# 5_cyber60-smk_periferals.net
KiCad netlist of a schematic drawn in Altium Designer
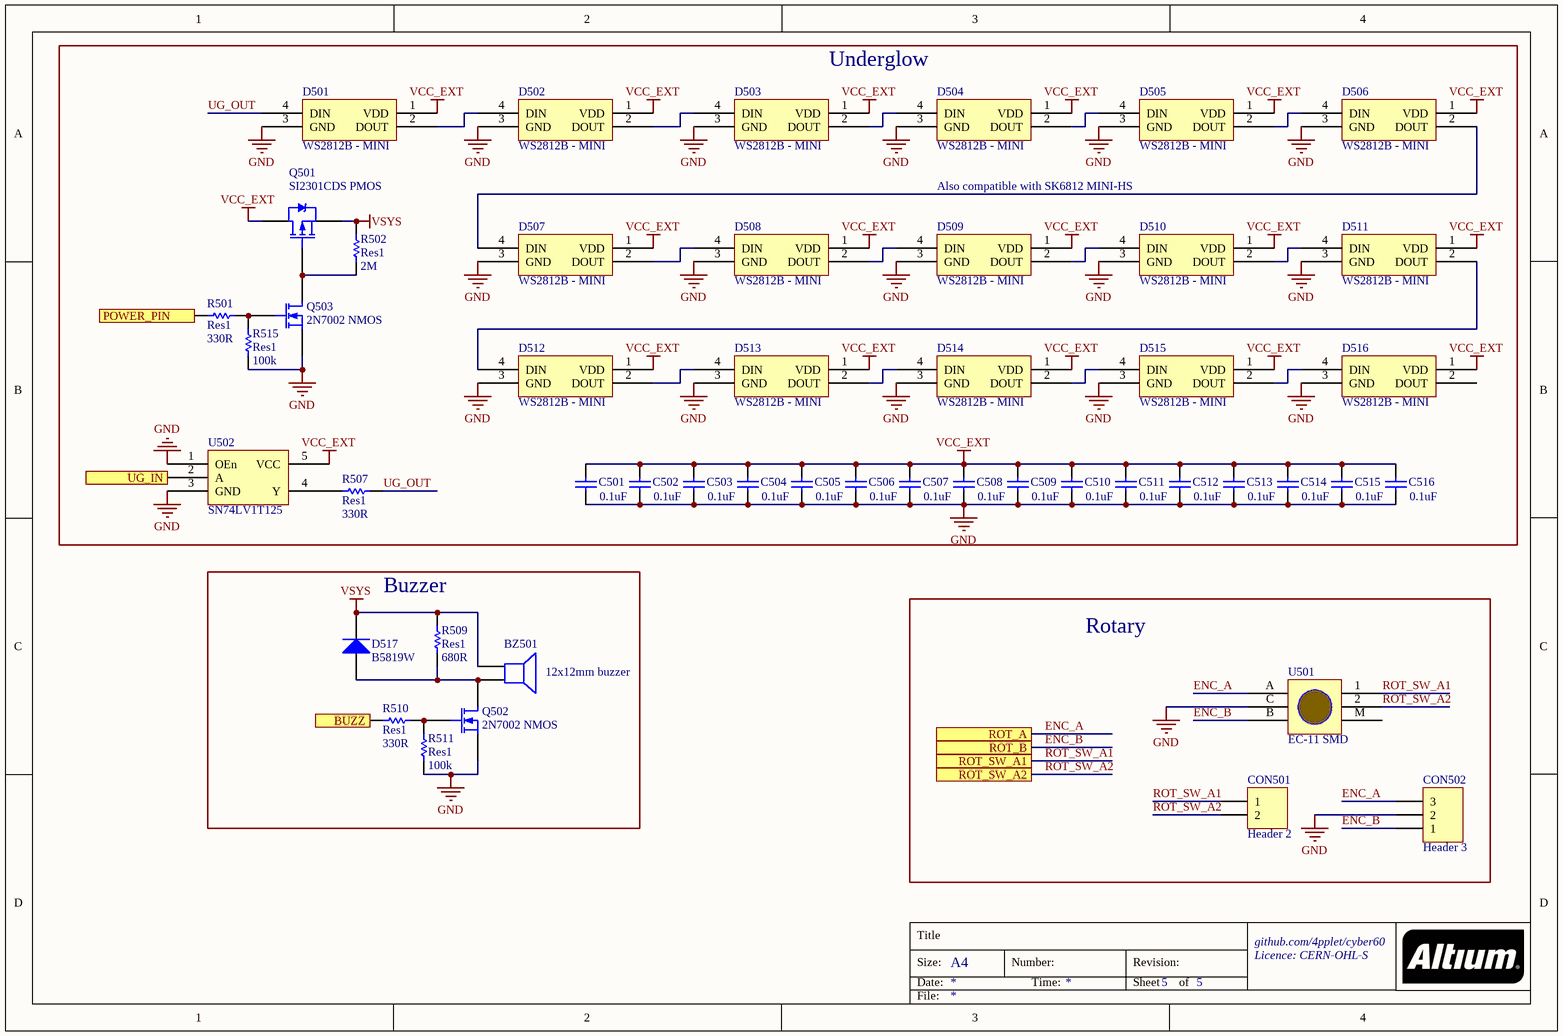
[diagram p0: 5_cyber60-smk_periferals.SchDoc]

(export (version "E")
  (design (tool "Eeschema 10.0.6"))
  (components
    (comp (ref "BZ501")
      (value "12x12mm buzzer")
      (footprint "buzzer 12x12")
      (description "Loudspeaker")
      (fields (field (name "LCSC PART #") "C409829") (field (name "MRF.PART") "YS-SBZ1230"))
      (libsource (lib "Miscellaneous Devices") (part "Speaker"))
    )
    (comp (ref "C501")
      (value "0.1uF")
      (footprint "C0603[1608]")
      (description "Capacitor")
      (fields (field (name "MFG") "KEMET") (field (name "LCSC PART #") "C14663"))
      (libsource (lib "Miscellaneous Devices") (part "Cap"))
    )
    (comp (ref "C502")
      (value "0.1uF")
      (footprint "C0603[1608]")
      (description "Capacitor")
      (fields (field (name "MFG") "KEMET") (field (name "LCSC PART #") "C14663"))
      (libsource (lib "Miscellaneous Devices") (part "Cap"))
    )
    (comp (ref "C503")
      (value "0.1uF")
      (footprint "C0603[1608]")
      (description "Capacitor")
      (fields (field (name "MFG") "KEMET") (field (name "LCSC PART #") "C14663"))
      (libsource (lib "Miscellaneous Devices") (part "Cap"))
    )
    (comp (ref "C504")
      (value "0.1uF")
      (footprint "C0603[1608]")
      (description "Capacitor")
      (fields (field (name "MFG") "KEMET") (field (name "LCSC PART #") "C14663"))
      (libsource (lib "Miscellaneous Devices") (part "Cap"))
    )
    (comp (ref "C505")
      (value "0.1uF")
      (footprint "C0603[1608]")
      (description "Capacitor")
      (fields (field (name "MFG") "KEMET") (field (name "LCSC PART #") "C14663"))
      (libsource (lib "Miscellaneous Devices") (part "Cap"))
    )
    (comp (ref "C506")
      (value "0.1uF")
      (footprint "C0603[1608]")
      (description "Capacitor")
      (fields (field (name "MFG") "KEMET") (field (name "LCSC PART #") "C14663"))
      (libsource (lib "Miscellaneous Devices") (part "Cap"))
    )
    (comp (ref "C507")
      (value "0.1uF")
      (footprint "C0603[1608]")
      (description "Capacitor")
      (fields (field (name "MFG") "KEMET") (field (name "LCSC PART #") "C14663"))
      (libsource (lib "Miscellaneous Devices") (part "Cap"))
    )
    (comp (ref "C508")
      (value "0.1uF")
      (footprint "C0603[1608]")
      (description "Capacitor")
      (fields (field (name "MFG") "KEMET") (field (name "LCSC PART #") "C14663"))
      (libsource (lib "Miscellaneous Devices") (part "Cap"))
    )
    (comp (ref "C509")
      (value "0.1uF")
      (footprint "C0603[1608]")
      (description "Capacitor")
      (fields (field (name "MFG") "KEMET") (field (name "LCSC PART #") "C14663"))
      (libsource (lib "Miscellaneous Devices") (part "Cap"))
    )
    (comp (ref "C510")
      (value "0.1uF")
      (footprint "C0603[1608]")
      (description "Capacitor")
      (fields (field (name "MFG") "KEMET") (field (name "LCSC PART #") "C14663"))
      (libsource (lib "Miscellaneous Devices") (part "Cap"))
    )
    (comp (ref "C511")
      (value "0.1uF")
      (footprint "C0603[1608]")
      (description "Capacitor")
      (fields (field (name "MFG") "KEMET") (field (name "LCSC PART #") "C14663"))
      (libsource (lib "Miscellaneous Devices") (part "Cap"))
    )
    (comp (ref "C512")
      (value "0.1uF")
      (footprint "C0603[1608]")
      (description "Capacitor")
      (fields (field (name "MFG") "KEMET") (field (name "LCSC PART #") "C14663"))
      (libsource (lib "Miscellaneous Devices") (part "Cap"))
    )
    (comp (ref "C513")
      (value "0.1uF")
      (footprint "C0603[1608]")
      (description "Capacitor")
      (fields (field (name "MFG") "KEMET") (field (name "LCSC PART #") "C14663"))
      (libsource (lib "Miscellaneous Devices") (part "Cap"))
    )
    (comp (ref "C514")
      (value "0.1uF")
      (footprint "C0603[1608]")
      (description "Capacitor")
      (fields (field (name "MFG") "KEMET") (field (name "LCSC PART #") "C14663"))
      (libsource (lib "Miscellaneous Devices") (part "Cap"))
    )
    (comp (ref "C515")
      (value "0.1uF")
      (footprint "C0603[1608]")
      (description "Capacitor")
      (fields (field (name "MFG") "KEMET") (field (name "LCSC PART #") "C14663"))
      (libsource (lib "Miscellaneous Devices") (part "Cap"))
    )
    (comp (ref "C516")
      (value "0.1uF")
      (footprint "C0603[1608]")
      (description "Capacitor")
      (fields (field (name "MFG") "KEMET") (field (name "LCSC PART #") "C14663"))
      (libsource (lib "Miscellaneous Devices") (part "Cap"))
    )
    (comp (ref "CON501")
      (value "Header 2")
      (footprint "HDR1X2")
      (description "Header, 2-Pin")
      (libsource (lib "Miscellaneous Connectors") (part "Header 2"))
    )
    (comp (ref "CON502")
      (value "Header 3")
      (footprint "HDR1X3")
      (description "Header, 3-Pin")
      (libsource (lib "Miscellaneous Connectors") (part "Header 3"))
    )
    (comp (ref "D501")
      (value "WS2812B - MINI")
      (footprint "WS2812B - 2020")
      (fields (field (name "LCSC PART #") "C965556") (field (name "MRF.PART") "WS2812C-2020"))
      (libsource (lib "Keebs") (part "WS2812B"))
    )
    (comp (ref "D502")
      (value "WS2812B - MINI")
      (footprint "WS2812B - 2020")
      (fields (field (name "LCSC PART #") "C965556") (field (name "MRF.PART") "WS2812C-2020"))
      (libsource (lib "Keebs") (part "WS2812B"))
    )
    (comp (ref "D503")
      (value "WS2812B - MINI")
      (footprint "WS2812B - 2020")
      (fields (field (name "LCSC PART #") "C965556") (field (name "MRF.PART") "WS2812C-2020"))
      (libsource (lib "Keebs") (part "WS2812B"))
    )
    (comp (ref "D504")
      (value "WS2812B - MINI")
      (footprint "WS2812B - 2020")
      (fields (field (name "LCSC PART #") "C965556") (field (name "MRF.PART") "WS2812C-2020"))
      (libsource (lib "Keebs") (part "WS2812B"))
    )
    (comp (ref "D505")
      (value "WS2812B - MINI")
      (footprint "WS2812B - 2020")
      (fields (field (name "LCSC PART #") "C965556") (field (name "MRF.PART") "WS2812C-2020"))
      (libsource (lib "Keebs") (part "WS2812B"))
    )
    (comp (ref "D506")
      (value "WS2812B - MINI")
      (footprint "WS2812B - 2020")
      (fields (field (name "LCSC PART #") "C965556") (field (name "MRF.PART") "WS2812C-2020"))
      (libsource (lib "Keebs") (part "WS2812B"))
    )
    (comp (ref "D507")
      (value "WS2812B - MINI")
      (footprint "WS2812B - 2020")
      (fields (field (name "LCSC PART #") "C965556") (field (name "MRF.PART") "WS2812C-2020"))
      (libsource (lib "Keebs") (part "WS2812B"))
    )
    (comp (ref "D508")
      (value "WS2812B - MINI")
      (footprint "WS2812B - 2020")
      (fields (field (name "LCSC PART #") "C965556") (field (name "MRF.PART") "WS2812C-2020"))
      (libsource (lib "Keebs") (part "WS2812B"))
    )
    (comp (ref "D509")
      (value "WS2812B - MINI")
      (footprint "WS2812B - 2020")
      (fields (field (name "LCSC PART #") "C965556") (field (name "MRF.PART") "WS2812C-2020"))
      (libsource (lib "Keebs") (part "WS2812B"))
    )
    (comp (ref "D510")
      (value "WS2812B - MINI")
      (footprint "WS2812B - 2020")
      (fields (field (name "LCSC PART #") "C965556") (field (name "MRF.PART") "WS2812C-2020"))
      (libsource (lib "Keebs") (part "WS2812B"))
    )
    (comp (ref "D511")
      (value "WS2812B - MINI")
      (footprint "WS2812B - 2020")
      (fields (field (name "LCSC PART #") "C965556") (field (name "MRF.PART") "WS2812C-2020"))
      (libsource (lib "Keebs") (part "WS2812B"))
    )
    (comp (ref "D512")
      (value "WS2812B - MINI")
      (footprint "WS2812B - 2020")
      (fields (field (name "LCSC PART #") "C965556") (field (name "MRF.PART") "WS2812C-2020"))
      (libsource (lib "Keebs") (part "WS2812B"))
    )
    (comp (ref "D513")
      (value "WS2812B - MINI")
      (footprint "WS2812B - 2020")
      (fields (field (name "LCSC PART #") "C965556") (field (name "MRF.PART") "WS2812C-2020"))
      (libsource (lib "Keebs") (part "WS2812B"))
    )
    (comp (ref "D514")
      (value "WS2812B - MINI")
      (footprint "WS2812B - 2020")
      (fields (field (name "LCSC PART #") "C965556") (field (name "MRF.PART") "WS2812C-2020"))
      (libsource (lib "Keebs") (part "WS2812B"))
    )
    (comp (ref "D515")
      (value "WS2812B - MINI")
      (footprint "WS2812B - 2020")
      (fields (field (name "LCSC PART #") "C965556") (field (name "MRF.PART") "WS2812C-2020"))
      (libsource (lib "Keebs") (part "WS2812B"))
    )
    (comp (ref "D516")
      (value "WS2812B - MINI")
      (footprint "WS2812B - 2020")
      (fields (field (name "LCSC PART #") "C965556") (field (name "MRF.PART") "WS2812C-2020"))
      (libsource (lib "Keebs") (part "WS2812B"))
    )
    (comp (ref "D517")
      (value "B5819W")
      (footprint "SOD-123")
      (description "Default Diode")
      (fields (field (name "LCSC PART #") "C8598"))
      (libsource (lib "Miscellaneous Devices") (part "Diode"))
    )
    (comp (ref "Q501")
      (value "SI2301CDS PMOS")
      (footprint "SOT-23-3")
      (description "P-Channel Power MOSFET")
      (fields (field (name "MRF.PART") "SI2301CDS-T1-GE3") (field (name "LCSC PART #") "C10487"))
      (libsource (lib "Miscellaneous Devices") (part "PMOS-2"))
    )
    (comp (ref "Q502")
      (value "2N7002 NMOS")
      (footprint "SOT-23-3")
      (description "N-Channel MOSFET")
      (fields (field (name "LCSC PART #") "C8545") (field (name "MRF.PART") "2N7002"))
      (libsource (lib "Miscellaneous Devices") (part "MOSFET-N"))
    )
    (comp (ref "Q503")
      (value "2N7002 NMOS")
      (footprint "SOT-23-3")
      (description "N-Channel MOSFET")
      (fields (field (name "LCSC PART #") "C8545") (field (name "MRF.PART") "2N7002"))
      (libsource (lib "Miscellaneous Devices") (part "MOSFET-N"))
    )
    (comp (ref "R501")
      (value "Res1")
      (footprint "R0603[1608]")
      (description "Resistor")
      (fields
        (field (name "ALTIUM_VALUE") "330R")
        (field (name "LCSC PART #") "C23138")
        (field (name "MRF.PART") "0603WAF3300T5E")
      )
      (libsource (lib "Miscellaneous Devices") (part "Res1"))
    )
    (comp (ref "R502")
      (value "Res1")
      (footprint "R0603[1608]")
      (description "Resistor")
      (fields
        (field (name "ALTIUM_VALUE") "2M")
        (field (name "MRF.PART") "0603WAF2004T5E")
        (field (name "LCSC PART #") "C22976")
      )
      (libsource (lib "Miscellaneous Devices") (part "Res1"))
    )
    (comp (ref "R507")
      (value "Res1")
      (footprint "R0603[1608]")
      (description "Resistor")
      (fields
        (field (name "ALTIUM_VALUE") "330R")
        (field (name "LCSC PART #") "C23138")
        (field (name "MRF.PART") "0603WAF3300T5E")
      )
      (libsource (lib "Miscellaneous Devices") (part "Res1"))
    )
    (comp (ref "R509")
      (value "Res1")
      (footprint "R0603[1608]")
      (description "Resistor")
      (fields
        (field (name "ALTIUM_VALUE") "680R")
        (field (name "MRF.PART") "0603WAF6800T5E")
        (field (name "LCSC PART #") "C23228")
      )
      (libsource (lib "Miscellaneous Devices") (part "Res1"))
    )
    (comp (ref "R510")
      (value "Res1")
      (footprint "R0603[1608]")
      (description "Resistor")
      (fields
        (field (name "ALTIUM_VALUE") "330R")
        (field (name "LCSC PART #") "C23138")
        (field (name "MRF.PART") "0603WAF3300T5E")
      )
      (libsource (lib "Miscellaneous Devices") (part "Res1"))
    )
    (comp (ref "R511")
      (value "Res1")
      (footprint "R0603[1608]")
      (description "Resistor")
      (fields
        (field (name "ALTIUM_VALUE") "100k")
        (field (name "MRF.PART") "0603WAF1003T5E")
        (field (name "LCSC PART #") "C25803")
      )
      (libsource (lib "Miscellaneous Devices") (part "Res1"))
    )
    (comp (ref "R515")
      (value "Res1")
      (footprint "R0603[1608]")
      (description "Resistor")
      (fields
        (field (name "ALTIUM_VALUE") "100k")
        (field (name "MRF.PART") "0603WAF1003T5E")
        (field (name "LCSC PART #") "C25803")
      )
      (libsource (lib "Miscellaneous Devices") (part "Res1"))
    )
    (comp (ref "U501") (value "EC-11 SMD") (footprint "EC11-SMD") (libsource (lib "Keebs") (part "EC-11")))
    (comp (ref "U502")
      (value "SN74LV1T125")
      (footprint "SOT-23-5")
      (description "SN74LV1T125 or SN74LV1T34. Connect OE to GND")
      (fields (field (name "LCSC PART #") "C473338") (field (name "MRF.PART") "SN74LV1T125DBVR"))
      (libsource (lib "Keebs") (part "SN74LV1T125"))
    )
  )
  (nets
    (net (code "1") (name "/BUZZ") (class "Default")
      (node (ref "R510") (pin "2") (pinfunction "2_2") (pintype "passive"))
    )
    (net (code "2") (name "/ENC_A") (class "Default")
      (node (ref "CON502") (pin "3") (pinfunction "3_3") (pintype "passive"))
      (node (ref "U501") (pin "A") (pinfunction "B_A") (pintype "passive"))
    )
    (net (code "3") (name "/ENC_B") (class "Default")
      (node (ref "CON502") (pin "1") (pinfunction "1_1") (pintype "passive"))
      (node (ref "U501") (pin "B") (pinfunction "B_B") (pintype "passive"))
    )
    (net (code "4") (name "/POWER_PIN") (class "Default")
      (node (ref "R501") (pin "1") (pinfunction "1_1") (pintype "passive"))
    )
    (net (code "5") (name "/ROT_SW_A1") (class "Default")
      (node (ref "CON501") (pin "1") (pinfunction "1_1") (pintype "passive"))
      (node (ref "U501") (pin "1") (pinfunction "1_1") (pintype "passive"))
    )
    (net (code "6") (name "/ROT_SW_A2") (class "Default")
      (node (ref "CON501") (pin "2") (pinfunction "2_2") (pintype "passive"))
      (node (ref "U501") (pin "2") (pinfunction "2_2") (pintype "passive"))
    )
    (net (code "7") (name "/UG_IN") (class "Default")
      (node (ref "U502") (pin "2") (pinfunction "A_2") (pintype "passive"))
    )
    (net (code "8") (name "/UG_OUT") (class "Default")
      (node (ref "D501") (pin "4") (pinfunction "DIN_4") (pintype "passive"))
      (node (ref "R507") (pin "1") (pinfunction "1_1") (pintype "passive"))
    )
    (net (code "9") (name "GND") (class "Default")
      (node (ref "C501") (pin "1") (pinfunction "1_1") (pintype "passive"))
      (node (ref "C502") (pin "1") (pinfunction "1_1") (pintype "passive"))
      (node (ref "C503") (pin "1") (pinfunction "1_1") (pintype "passive"))
      (node (ref "C504") (pin "1") (pinfunction "1_1") (pintype "passive"))
      (node (ref "C505") (pin "1") (pinfunction "1_1") (pintype "passive"))
      (node (ref "C506") (pin "1") (pinfunction "1_1") (pintype "passive"))
      (node (ref "C507") (pin "1") (pinfunction "1_1") (pintype "passive"))
      (node (ref "C508") (pin "1") (pinfunction "1_1") (pintype "passive"))
      (node (ref "C509") (pin "1") (pinfunction "1_1") (pintype "passive"))
      (node (ref "C510") (pin "1") (pinfunction "1_1") (pintype "passive"))
      (node (ref "C511") (pin "1") (pinfunction "1_1") (pintype "passive"))
      (node (ref "C512") (pin "1") (pinfunction "1_1") (pintype "passive"))
      (node (ref "C513") (pin "1") (pinfunction "1_1") (pintype "passive"))
      (node (ref "C514") (pin "1") (pinfunction "1_1") (pintype "passive"))
      (node (ref "C515") (pin "1") (pinfunction "1_1") (pintype "passive"))
      (node (ref "C516") (pin "1") (pinfunction "1_1") (pintype "passive"))
      (node (ref "CON502") (pin "2") (pinfunction "2_2") (pintype "passive"))
      (node (ref "D501") (pin "3") (pinfunction "GND_3") (pintype "passive"))
      (node (ref "D502") (pin "3") (pinfunction "GND_3") (pintype "passive"))
      (node (ref "D503") (pin "3") (pinfunction "GND_3") (pintype "passive"))
      (node (ref "D504") (pin "3") (pinfunction "GND_3") (pintype "passive"))
      (node (ref "D505") (pin "3") (pinfunction "GND_3") (pintype "passive"))
      (node (ref "D506") (pin "3") (pinfunction "GND_3") (pintype "passive"))
      (node (ref "D507") (pin "3") (pinfunction "GND_3") (pintype "passive"))
      (node (ref "D508") (pin "3") (pinfunction "GND_3") (pintype "passive"))
      (node (ref "D509") (pin "3") (pinfunction "GND_3") (pintype "passive"))
      (node (ref "D510") (pin "3") (pinfunction "GND_3") (pintype "passive"))
      (node (ref "D511") (pin "3") (pinfunction "GND_3") (pintype "passive"))
      (node (ref "D512") (pin "3") (pinfunction "GND_3") (pintype "passive"))
      (node (ref "D513") (pin "3") (pinfunction "GND_3") (pintype "passive"))
      (node (ref "D514") (pin "3") (pinfunction "GND_3") (pintype "passive"))
      (node (ref "D515") (pin "3") (pinfunction "GND_3") (pintype "passive"))
      (node (ref "D516") (pin "3") (pinfunction "GND_3") (pintype "passive"))
      (node (ref "Q502") (pin "2") (pinfunction "S_2") (pintype "passive"))
      (node (ref "Q503") (pin "2") (pinfunction "S_2") (pintype "passive"))
      (node (ref "R511") (pin "2") (pinfunction "2_2") (pintype "passive"))
      (node (ref "R515") (pin "2") (pinfunction "2_2") (pintype "passive"))
      (node (ref "U501") (pin "C") (pinfunction "C_C") (pintype "passive"))
      (node (ref "U502") (pin "1") (pinfunction "OEn_1") (pintype "passive"))
      (node (ref "U502") (pin "3") (pinfunction "GND_3") (pintype "passive"))
    )
    (net (code "10") (name "Net-(D501-DOUT)") (class "Default")
      (node (ref "D501") (pin "2") (pinfunction "DOUT_2") (pintype "passive"))
      (node (ref "D502") (pin "4") (pinfunction "DIN_4") (pintype "passive"))
    )
    (net (code "11") (name "Net-(D502-DOUT)") (class "Default")
      (node (ref "D502") (pin "2") (pinfunction "DOUT_2") (pintype "passive"))
      (node (ref "D503") (pin "4") (pinfunction "DIN_4") (pintype "passive"))
    )
    (net (code "12") (name "Net-(D503-DOUT)") (class "Default")
      (node (ref "D503") (pin "2") (pinfunction "DOUT_2") (pintype "passive"))
      (node (ref "D504") (pin "4") (pinfunction "DIN_4") (pintype "passive"))
    )
    (net (code "13") (name "Net-(D504-DOUT)") (class "Default")
      (node (ref "D504") (pin "2") (pinfunction "DOUT_2") (pintype "passive"))
      (node (ref "D505") (pin "4") (pinfunction "DIN_4") (pintype "passive"))
    )
    (net (code "14") (name "Net-(D505-DOUT)") (class "Default")
      (node (ref "D505") (pin "2") (pinfunction "DOUT_2") (pintype "passive"))
      (node (ref "D506") (pin "4") (pinfunction "DIN_4") (pintype "passive"))
    )
    (net (code "15") (name "Net-(D506-DOUT)") (class "Default")
      (node (ref "D506") (pin "2") (pinfunction "DOUT_2") (pintype "passive"))
      (node (ref "D507") (pin "4") (pinfunction "DIN_4") (pintype "passive"))
    )
    (net (code "16") (name "Net-(D507-DOUT)") (class "Default")
      (node (ref "D507") (pin "2") (pinfunction "DOUT_2") (pintype "passive"))
      (node (ref "D508") (pin "4") (pinfunction "DIN_4") (pintype "passive"))
    )
    (net (code "17") (name "Net-(D508-DOUT)") (class "Default")
      (node (ref "D508") (pin "2") (pinfunction "DOUT_2") (pintype "passive"))
      (node (ref "D509") (pin "4") (pinfunction "DIN_4") (pintype "passive"))
    )
    (net (code "18") (name "Net-(D509-DOUT)") (class "Default")
      (node (ref "D509") (pin "2") (pinfunction "DOUT_2") (pintype "passive"))
      (node (ref "D510") (pin "4") (pinfunction "DIN_4") (pintype "passive"))
    )
    (net (code "19") (name "Net-(D510-DOUT)") (class "Default")
      (node (ref "D510") (pin "2") (pinfunction "DOUT_2") (pintype "passive"))
      (node (ref "D511") (pin "4") (pinfunction "DIN_4") (pintype "passive"))
    )
    (net (code "20") (name "Net-(D511-DOUT)") (class "Default")
      (node (ref "D511") (pin "2") (pinfunction "DOUT_2") (pintype "passive"))
      (node (ref "D512") (pin "4") (pinfunction "DIN_4") (pintype "passive"))
    )
    (net (code "21") (name "Net-(D512-DOUT)") (class "Default")
      (node (ref "D512") (pin "2") (pinfunction "DOUT_2") (pintype "passive"))
      (node (ref "D513") (pin "4") (pinfunction "DIN_4") (pintype "passive"))
    )
    (net (code "22") (name "Net-(D513-DOUT)") (class "Default")
      (node (ref "D513") (pin "2") (pinfunction "DOUT_2") (pintype "passive"))
      (node (ref "D514") (pin "4") (pinfunction "DIN_4") (pintype "passive"))
    )
    (net (code "23") (name "Net-(D514-DOUT)") (class "Default")
      (node (ref "D514") (pin "2") (pinfunction "DOUT_2") (pintype "passive"))
      (node (ref "D515") (pin "4") (pinfunction "DIN_4") (pintype "passive"))
    )
    (net (code "24") (name "Net-(D515-DOUT)") (class "Default")
      (node (ref "D515") (pin "2") (pinfunction "DOUT_2") (pintype "passive"))
      (node (ref "D516") (pin "4") (pinfunction "DIN_4") (pintype "passive"))
    )
    (net (code "25") (name "Net-(D517-A)") (class "Default")
      (node (ref "BZ501") (pin "2") (pinfunction "2_2") (pintype "passive"))
      (node (ref "D517") (pin "1") (pinfunction "A_1") (pintype "passive"))
      (node (ref "Q502") (pin "3") (pinfunction "D_3") (pintype "passive"))
      (node (ref "R509") (pin "2") (pinfunction "2_2") (pintype "passive"))
    )
    (net (code "26") (name "Net-(Q501-G)") (class "Default")
      (node (ref "Q501") (pin "1") (pinfunction "G_1") (pintype "passive"))
      (node (ref "Q503") (pin "3") (pinfunction "D_3") (pintype "passive"))
      (node (ref "R502") (pin "1") (pinfunction "1_1") (pintype "passive"))
    )
    (net (code "27") (name "Net-(Q502-G)") (class "Default")
      (node (ref "Q502") (pin "1") (pinfunction "G_1") (pintype "passive"))
      (node (ref "R510") (pin "1") (pinfunction "1_1") (pintype "passive"))
      (node (ref "R511") (pin "1") (pinfunction "1_1") (pintype "passive"))
    )
    (net (code "28") (name "Net-(Q503-G)") (class "Default")
      (node (ref "Q503") (pin "1") (pinfunction "G_1") (pintype "passive"))
      (node (ref "R501") (pin "2") (pinfunction "2_2") (pintype "passive"))
      (node (ref "R515") (pin "1") (pinfunction "1_1") (pintype "passive"))
    )
    (net (code "29") (name "Net-(U502-Y)") (class "Default")
      (node (ref "R507") (pin "2") (pinfunction "2_2") (pintype "passive"))
      (node (ref "U502") (pin "4") (pinfunction "Y_4") (pintype "passive"))
    )
    (net (code "30") (name "VCC_EXT") (class "Default")
      (node (ref "C501") (pin "2") (pinfunction "2_2") (pintype "passive"))
      (node (ref "C502") (pin "2") (pinfunction "2_2") (pintype "passive"))
      (node (ref "C503") (pin "2") (pinfunction "2_2") (pintype "passive"))
      (node (ref "C504") (pin "2") (pinfunction "2_2") (pintype "passive"))
      (node (ref "C505") (pin "2") (pinfunction "2_2") (pintype "passive"))
      (node (ref "C506") (pin "2") (pinfunction "2_2") (pintype "passive"))
      (node (ref "C507") (pin "2") (pinfunction "2_2") (pintype "passive"))
      (node (ref "C508") (pin "2") (pinfunction "2_2") (pintype "passive"))
      (node (ref "C509") (pin "2") (pinfunction "2_2") (pintype "passive"))
      (node (ref "C510") (pin "2") (pinfunction "2_2") (pintype "passive"))
      (node (ref "C511") (pin "2") (pinfunction "2_2") (pintype "passive"))
      (node (ref "C512") (pin "2") (pinfunction "2_2") (pintype "passive"))
      (node (ref "C513") (pin "2") (pinfunction "2_2") (pintype "passive"))
      (node (ref "C514") (pin "2") (pinfunction "2_2") (pintype "passive"))
      (node (ref "C515") (pin "2") (pinfunction "2_2") (pintype "passive"))
      (node (ref "C516") (pin "2") (pinfunction "2_2") (pintype "passive"))
      (node (ref "D501") (pin "1") (pinfunction "VDD_1") (pintype "passive"))
      (node (ref "D502") (pin "1") (pinfunction "VDD_1") (pintype "passive"))
      (node (ref "D503") (pin "1") (pinfunction "VDD_1") (pintype "passive"))
      (node (ref "D504") (pin "1") (pinfunction "VDD_1") (pintype "passive"))
      (node (ref "D505") (pin "1") (pinfunction "VDD_1") (pintype "passive"))
      (node (ref "D506") (pin "1") (pinfunction "VDD_1") (pintype "passive"))
      (node (ref "D507") (pin "1") (pinfunction "VDD_1") (pintype "passive"))
      (node (ref "D508") (pin "1") (pinfunction "VDD_1") (pintype "passive"))
      (node (ref "D509") (pin "1") (pinfunction "VDD_1") (pintype "passive"))
      (node (ref "D510") (pin "1") (pinfunction "VDD_1") (pintype "passive"))
      (node (ref "D511") (pin "1") (pinfunction "VDD_1") (pintype "passive"))
      (node (ref "D512") (pin "1") (pinfunction "VDD_1") (pintype "passive"))
      (node (ref "D513") (pin "1") (pinfunction "VDD_1") (pintype "passive"))
      (node (ref "D514") (pin "1") (pinfunction "VDD_1") (pintype "passive"))
      (node (ref "D515") (pin "1") (pinfunction "VDD_1") (pintype "passive"))
      (node (ref "D516") (pin "1") (pinfunction "VDD_1") (pintype "passive"))
      (node (ref "Q501") (pin "3") (pinfunction "D_3") (pintype "passive"))
      (node (ref "U502") (pin "5") (pinfunction "VCC_5") (pintype "passive"))
    )
    (net (code "31") (name "VSYS") (class "Default")
      (node (ref "BZ501") (pin "1") (pinfunction "1_1") (pintype "passive"))
      (node (ref "D517") (pin "2") (pinfunction "K_2") (pintype "passive"))
      (node (ref "Q501") (pin "2") (pinfunction "S_2") (pintype "passive"))
      (node (ref "R502") (pin "2") (pinfunction "2_2") (pintype "passive"))
      (node (ref "R509") (pin "1") (pinfunction "1_1") (pintype "passive"))
    )
    (net (code "32") (name "unconnected-(D516-DOUT-Pad2)") (class "Default")
      (node (ref "D516") (pin "2") (pinfunction "DOUT_2") (pintype "passive"))
    )
    (net (code "33") (name "unconnected-(U501-PadM)") (class "Default")
      (node (ref "U501") (pin "M") (pinfunction "M_M") (pintype "passive"))
    )
  )
)
